# HeaderA.net
KiCad netlist of a schematic drawn in Altium Designer
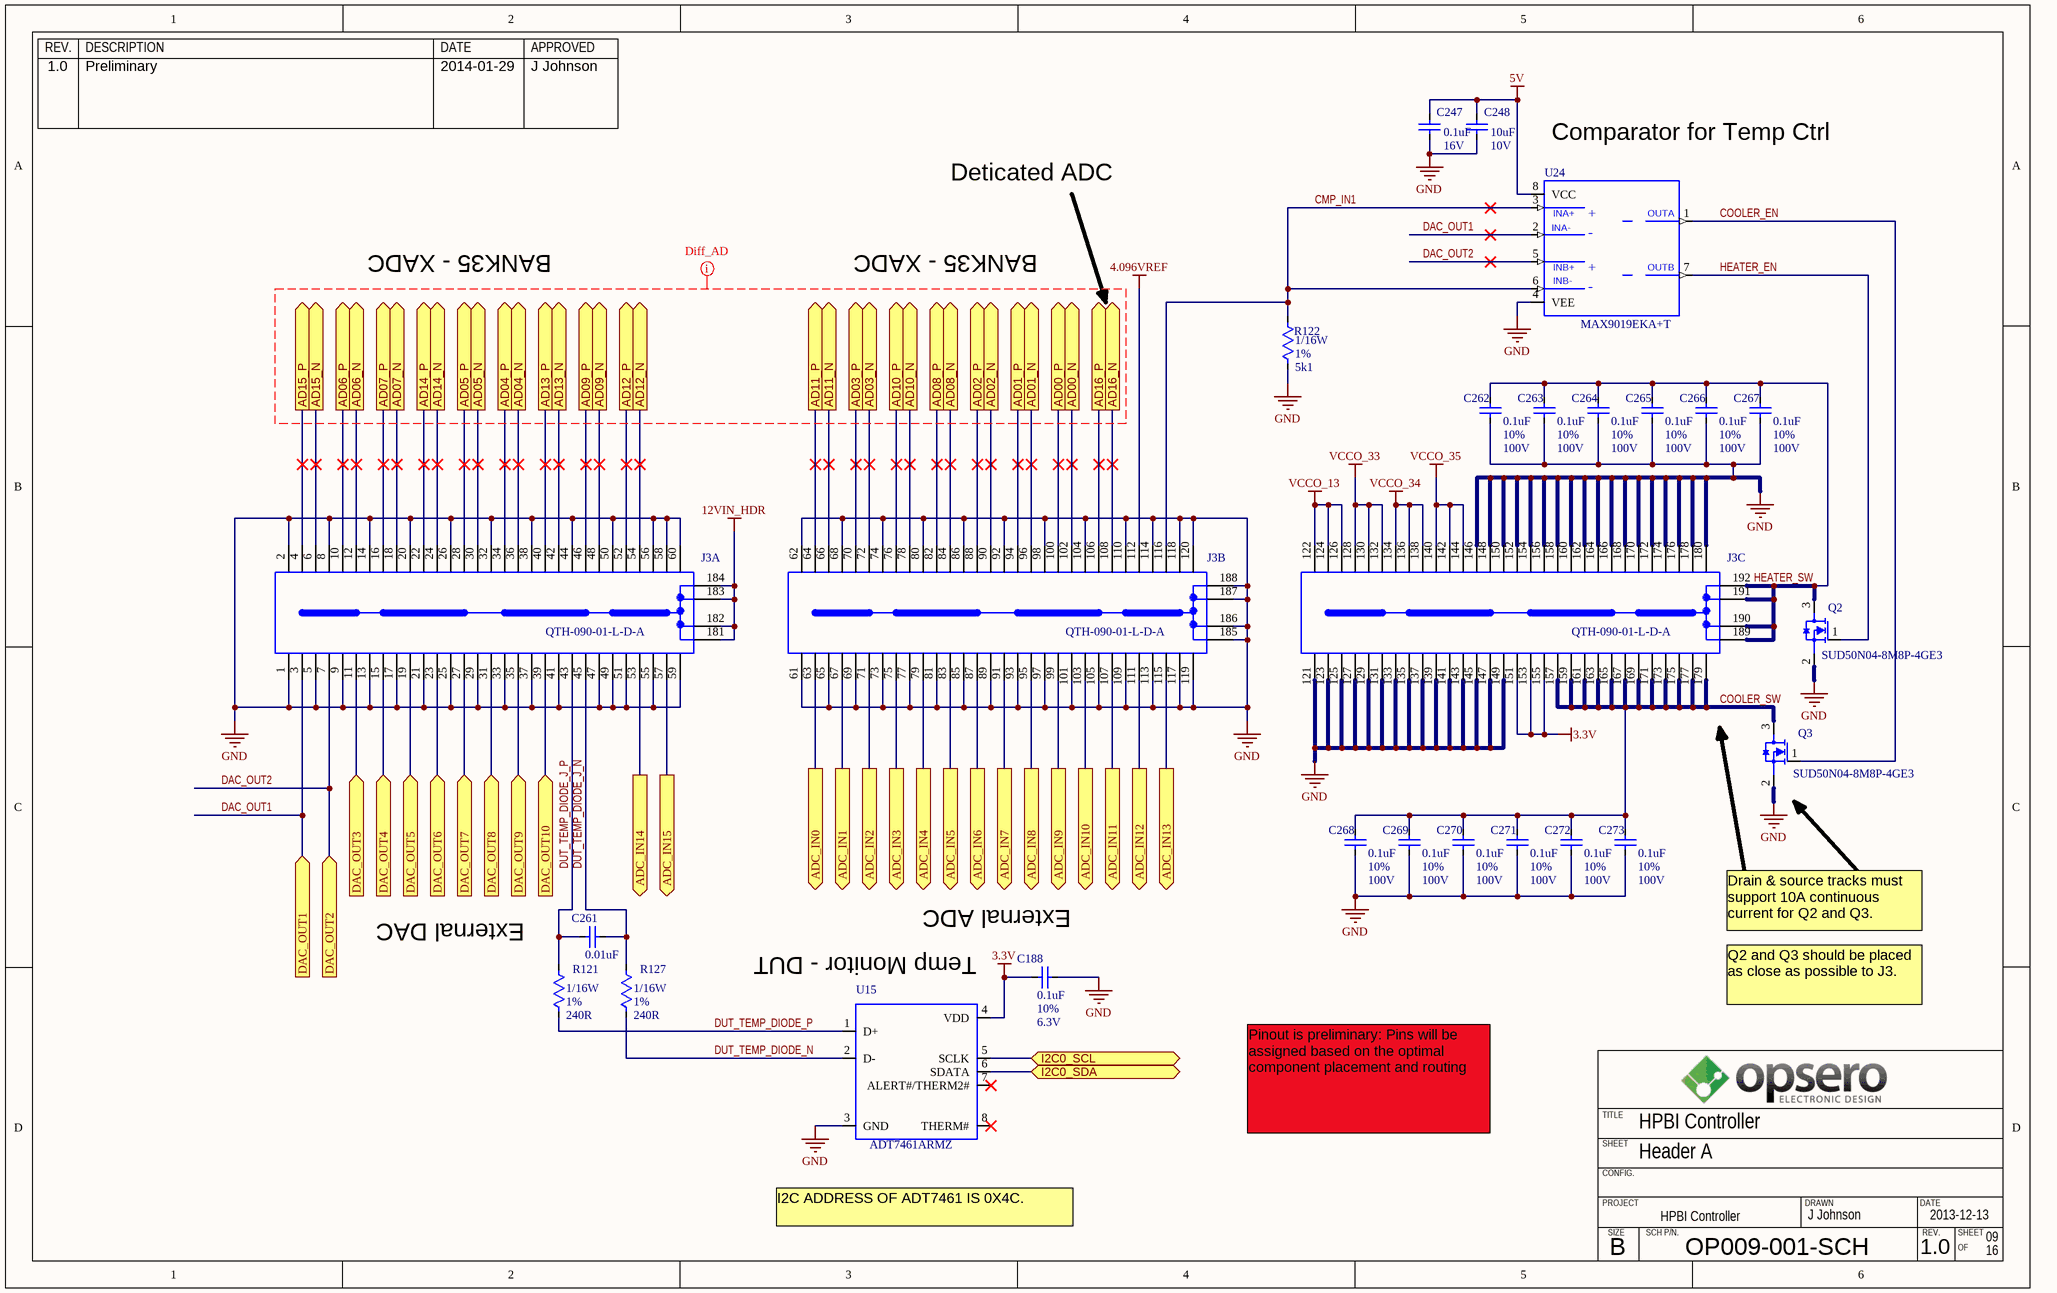
[diagram p0: HeaderA.SchDoc]

(export (version "E")
  (design (tool "Eeschema 10.0.6"))
  (components
    (comp (ref "C188")
      (value "0.1uF")
      (footprint "CAPC0603X33N")
      (description "Capacitor ceramic, X5R, 0.1uF, 6.3V, 10%, -55 to +125 C, EIA0201")
      (fields
        (field (name "TOLERANCE") "10%")
        (field (name "VOLTAGE") "6.3V")
        (field (name "Comment") "CAPACITOR_NP_TYPE1")
      )
      (libsource (lib "parts") (part "CAPACITOR_NP_TYPE1"))
    )
    (comp (ref "C247")
      (value "0.1uF")
      (footprint "CAPC1005X33N")
      (description "Capacitor ceramic, X7R, 0.1uF, 16V, 10%, -55 to +125 C, EIA0402")
      (fields
        (field (name "TOLERANCE") "10%")
        (field (name "VOLTAGE") "16V")
        (field (name "Comment") "CAPACITOR_NP_TYPE1")
      )
      (libsource (lib "parts") (part "CAPACITOR_NP_TYPE1"))
    )
    (comp (ref "C248")
      (value "10uF")
      (footprint "CAPC1608X38N")
      (description "Capacitor ceramic, X5R, 10uF, 10V, 10%, -55 to +85 C, EIA0603")
      (fields
        (field (name "TOLERANCE") "10%")
        (field (name "VOLTAGE") "10V")
        (field (name "Comment") "CAPACITOR_NP_TYPE1")
      )
      (libsource (lib "parts") (part "CAPACITOR_NP_TYPE1"))
    )
    (comp (ref "C261")
      (value "0.01uF")
      (footprint "CAPC1005X33N")
      (description "Capacitor ceramic, X7R, 0.01uF, 50V, 10%, -55 to +125 C, EIA0402")
      (fields (field (name "TOLERANCE") "10%") (field (name "VOLTAGE") "50V"))
      (libsource (lib "parts") (part "CAPACITOR_NP_TYPE1"))
    )
    (comp (ref "C262")
      (value "0.1uF")
      (footprint "CAPC1608X38N")
      (description "Capacitor ceramic, X7R, 0.1uF, 100V, 10%, -55 to +125 C, EIA0603")
      (fields
        (field (name "TOLERANCE") "10%")
        (field (name "VOLTAGE") "100V")
        (field (name "Comment") "CAPACITOR_NP_TYPE1")
      )
      (libsource (lib "parts") (part "CAPACITOR_NP_TYPE1"))
    )
    (comp (ref "C263")
      (value "0.1uF")
      (footprint "CAPC1608X38N")
      (description "Capacitor ceramic, X7R, 0.1uF, 100V, 10%, -55 to +125 C, EIA0603")
      (fields
        (field (name "TOLERANCE") "10%")
        (field (name "VOLTAGE") "100V")
        (field (name "Comment") "CAPACITOR_NP_TYPE1")
      )
      (libsource (lib "parts") (part "CAPACITOR_NP_TYPE1"))
    )
    (comp (ref "C264")
      (value "0.1uF")
      (footprint "CAPC1608X38N")
      (description "Capacitor ceramic, X7R, 0.1uF, 100V, 10%, -55 to +125 C, EIA0603")
      (fields
        (field (name "TOLERANCE") "10%")
        (field (name "VOLTAGE") "100V")
        (field (name "Comment") "CAPACITOR_NP_TYPE1")
      )
      (libsource (lib "parts") (part "CAPACITOR_NP_TYPE1"))
    )
    (comp (ref "C265")
      (value "0.1uF")
      (footprint "CAPC1608X38N")
      (description "Capacitor ceramic, X7R, 0.1uF, 100V, 10%, -55 to +125 C, EIA0603")
      (fields
        (field (name "TOLERANCE") "10%")
        (field (name "VOLTAGE") "100V")
        (field (name "Comment") "CAPACITOR_NP_TYPE1")
      )
      (libsource (lib "parts") (part "CAPACITOR_NP_TYPE1"))
    )
    (comp (ref "C266")
      (value "0.1uF")
      (footprint "CAPC1608X38N")
      (description "Capacitor ceramic, X7R, 0.1uF, 100V, 10%, -55 to +125 C, EIA0603")
      (fields
        (field (name "TOLERANCE") "10%")
        (field (name "VOLTAGE") "100V")
        (field (name "Comment") "CAPACITOR_NP_TYPE1")
      )
      (libsource (lib "parts") (part "CAPACITOR_NP_TYPE1"))
    )
    (comp (ref "C267")
      (value "0.1uF")
      (footprint "CAPC1608X38N")
      (description "Capacitor ceramic, X7R, 0.1uF, 100V, 10%, -55 to +125 C, EIA0603")
      (fields
        (field (name "TOLERANCE") "10%")
        (field (name "VOLTAGE") "100V")
        (field (name "Comment") "CAPACITOR_NP_TYPE1")
      )
      (libsource (lib "parts") (part "CAPACITOR_NP_TYPE1"))
    )
    (comp (ref "C268")
      (value "0.1uF")
      (footprint "CAPC1608X38N")
      (description "Capacitor ceramic, X7R, 0.1uF, 100V, 10%, -55 to +125 C, EIA0603")
      (fields
        (field (name "TOLERANCE") "10%")
        (field (name "VOLTAGE") "100V")
        (field (name "Comment") "CAPACITOR_NP_TYPE1")
      )
      (libsource (lib "parts") (part "CAPACITOR_NP_TYPE1"))
    )
    (comp (ref "C269")
      (value "0.1uF")
      (footprint "CAPC1608X38N")
      (description "Capacitor ceramic, X7R, 0.1uF, 100V, 10%, -55 to +125 C, EIA0603")
      (fields
        (field (name "TOLERANCE") "10%")
        (field (name "VOLTAGE") "100V")
        (field (name "Comment") "CAPACITOR_NP_TYPE1")
      )
      (libsource (lib "parts") (part "CAPACITOR_NP_TYPE1"))
    )
    (comp (ref "C270")
      (value "0.1uF")
      (footprint "CAPC1608X38N")
      (description "Capacitor ceramic, X7R, 0.1uF, 100V, 10%, -55 to +125 C, EIA0603")
      (fields
        (field (name "TOLERANCE") "10%")
        (field (name "VOLTAGE") "100V")
        (field (name "Comment") "CAPACITOR_NP_TYPE1")
      )
      (libsource (lib "parts") (part "CAPACITOR_NP_TYPE1"))
    )
    (comp (ref "C271")
      (value "0.1uF")
      (footprint "CAPC1608X38N")
      (description "Capacitor ceramic, X7R, 0.1uF, 100V, 10%, -55 to +125 C, EIA0603")
      (fields
        (field (name "TOLERANCE") "10%")
        (field (name "VOLTAGE") "100V")
        (field (name "Comment") "CAPACITOR_NP_TYPE1")
      )
      (libsource (lib "parts") (part "CAPACITOR_NP_TYPE1"))
    )
    (comp (ref "C272")
      (value "0.1uF")
      (footprint "CAPC1608X38N")
      (description "Capacitor ceramic, X7R, 0.1uF, 100V, 10%, -55 to +125 C, EIA0603")
      (fields
        (field (name "TOLERANCE") "10%")
        (field (name "VOLTAGE") "100V")
        (field (name "Comment") "CAPACITOR_NP_TYPE1")
      )
      (libsource (lib "parts") (part "CAPACITOR_NP_TYPE1"))
    )
    (comp (ref "C273")
      (value "0.1uF")
      (footprint "CAPC1608X38N")
      (description "Capacitor ceramic, X7R, 0.1uF, 100V, 10%, -55 to +125 C, EIA0603")
      (fields
        (field (name "TOLERANCE") "10%")
        (field (name "VOLTAGE") "100V")
        (field (name "Comment") "CAPACITOR_NP_TYPE1")
      )
      (libsource (lib "parts") (part "CAPACITOR_NP_TYPE1"))
    )
    (comp (ref "J3")
      (value "QTH-090-01-L-D-A")
      (footprint "QTH-090-01-L-D-A")
      (description "Connector Header HS .5mm 180 pin DL AU")
      (libsource (lib "parts") (part "QTH-090-01-L-D-A"))
    )
    (comp (ref "Q2")
      (value "SUD50N04-8M8P-4GE3")
      (footprint "TO228P1041X238-3N")
      (description "Transistor MOSFET, N-Channel, 40V, 50A, -55 to +150 C, 48W, TO-252")
      (fields (field (name "POWER") "48W") (field (name "VOLTAGE") "40V"))
      (libsource (lib "parts") (part "TRANS_MOSFET_N-CH_TYPE2"))
    )
    (comp (ref "Q3")
      (value "SUD50N04-8M8P-4GE3")
      (footprint "TO228P1041X238-3N")
      (description "Transistor MOSFET, N-Channel, 40V, 50A, -55 to +150 C, 48W, TO-252")
      (fields (field (name "POWER") "48W") (field (name "VOLTAGE") "40V"))
      (libsource (lib "parts") (part "TRANS_MOSFET_N-CH_TYPE2"))
    )
    (comp (ref "R121")
      (value "240R")
      (footprint "RESC1005X33N")
      (description "Resistor, 240R, 1/16W, 1%, -50 to +155 C, EIA0402, EIA(M)1005")
      (fields (field (name "VOLTAGE") "50V") (field (name "POWER") "1/16W") (field (name "TOLERANCE") "1%"))
      (libsource (lib "parts") (part "RESISTOR_TYPE1"))
    )
    (comp (ref "R122")
      (value "5k1")
      (footprint "RESC1005X33N")
      (description "Resistor, 5k10, 1/16W, 1%, -50 to +155 C, EIA0402, EIA(M)1005")
      (fields (field (name "VOLTAGE") "50V") (field (name "POWER") "1/16W") (field (name "TOLERANCE") "1%"))
      (libsource (lib "parts") (part "RESISTOR_TYPE1"))
    )
    (comp (ref "R127")
      (value "240R")
      (footprint "RESC1005X33N")
      (description "Resistor, 240R, 1/16W, 1%, -50 to +155 C, EIA0402, EIA(M)1005")
      (fields (field (name "VOLTAGE") "50V") (field (name "POWER") "1/16W") (field (name "TOLERANCE") "1%"))
      (libsource (lib "parts") (part "RESISTOR_TYPE1"))
    )
    (comp (ref "U15")
      (value "ADT7461ARMZ")
      (footprint "SOP65P490X110-8N")
      (description "Temperature monitor 1C, MSOP8")
      (fields (field (name "POWER") "Pow") (field (name "VOLTAGE") "Vol"))
      (libsource (lib "parts") (part "ADT7461"))
    )
    (comp (ref "U24")
      (value "MAX9019EKA+T")
      (footprint "SOT65P280X145-8AN")
      (description "Comparator, Dual, Push-pull, 1.8V to 5.5V, 50mA, -40 to +85 C, , SOT-23-8")
      (fields (field (name "POWER") "Pow") (field (name "VOLTAGE") "1.8V to 5.5V"))
      (libsource (lib "parts") (part "MAX9019"))
    )
  )
  (nets
    (net (code "1") (name "/AD00_N") (class "Default")
      (node (ref "J3") (pin "102") (pinfunction "102_102") (pintype "passive"))
    )
    (net (code "2") (name "/AD00_P") (class "Default")
      (node (ref "J3") (pin "100") (pinfunction "100_100") (pintype "passive"))
    )
    (net (code "3") (name "/AD01_N") (class "Default")
      (node (ref "J3") (pin "96") (pinfunction "96_96") (pintype "passive"))
    )
    (net (code "4") (name "/AD01_P") (class "Default")
      (node (ref "J3") (pin "94") (pinfunction "94_94") (pintype "passive"))
    )
    (net (code "5") (name "/AD02_N") (class "Default")
      (node (ref "J3") (pin "90") (pinfunction "90_90") (pintype "passive"))
    )
    (net (code "6") (name "/AD02_P") (class "Default")
      (node (ref "J3") (pin "88") (pinfunction "88_88") (pintype "passive"))
    )
    (net (code "7") (name "/AD03_N") (class "Default")
      (node (ref "J3") (pin "72") (pinfunction "72_72") (pintype "passive"))
    )
    (net (code "8") (name "/AD03_P") (class "Default")
      (node (ref "J3") (pin "70") (pinfunction "70_70") (pintype "passive"))
    )
    (net (code "9") (name "/AD04_N") (class "Default")
      (node (ref "J3") (pin "36") (pinfunction "36_36") (pintype "passive"))
    )
    (net (code "10") (name "/AD04_P") (class "Default")
      (node (ref "J3") (pin "34") (pinfunction "34_34") (pintype "passive"))
    )
    (net (code "11") (name "/AD05_N") (class "Default")
      (node (ref "J3") (pin "30") (pinfunction "30_30") (pintype "passive"))
    )
    (net (code "12") (name "/AD05_P") (class "Default")
      (node (ref "J3") (pin "28") (pinfunction "28_28") (pintype "passive"))
    )
    (net (code "13") (name "/AD06_N") (class "Default")
      (node (ref "J3") (pin "12") (pinfunction "12_12") (pintype "passive"))
    )
    (net (code "14") (name "/AD06_P") (class "Default")
      (node (ref "J3") (pin "10") (pinfunction "10_10") (pintype "passive"))
    )
    (net (code "15") (name "/AD07_N") (class "Default")
      (node (ref "J3") (pin "18") (pinfunction "18_18") (pintype "passive"))
    )
    (net (code "16") (name "/AD07_P") (class "Default")
      (node (ref "J3") (pin "16") (pinfunction "16_16") (pintype "passive"))
    )
    (net (code "17") (name "/AD08_N") (class "Default")
      (node (ref "J3") (pin "84") (pinfunction "84_84") (pintype "passive"))
    )
    (net (code "18") (name "/AD08_P") (class "Default")
      (node (ref "J3") (pin "82") (pinfunction "82_82") (pintype "passive"))
    )
    (net (code "19") (name "/AD09_N") (class "Default")
      (node (ref "J3") (pin "48") (pinfunction "48_48") (pintype "passive"))
    )
    (net (code "20") (name "/AD09_P") (class "Default")
      (node (ref "J3") (pin "46") (pinfunction "46_46") (pintype "passive"))
    )
    (net (code "21") (name "/AD10_N") (class "Default")
      (node (ref "J3") (pin "78") (pinfunction "78_78") (pintype "passive"))
    )
    (net (code "22") (name "/AD10_P") (class "Default")
      (node (ref "J3") (pin "76") (pinfunction "76_76") (pintype "passive"))
    )
    (net (code "23") (name "/AD11_N") (class "Default")
      (node (ref "J3") (pin "66") (pinfunction "66_66") (pintype "passive"))
    )
    (net (code "24") (name "/AD11_P") (class "Default")
      (node (ref "J3") (pin "64") (pinfunction "64_64") (pintype "passive"))
    )
    (net (code "25") (name "/AD12_N") (class "Default")
      (node (ref "J3") (pin "54") (pinfunction "54_54") (pintype "passive"))
    )
    (net (code "26") (name "/AD12_P") (class "Default")
      (node (ref "J3") (pin "52") (pinfunction "52_52") (pintype "passive"))
    )
    (net (code "27") (name "/AD13_N") (class "Default")
      (node (ref "J3") (pin "42") (pinfunction "42_42") (pintype "passive"))
    )
    (net (code "28") (name "/AD13_P") (class "Default")
      (node (ref "J3") (pin "40") (pinfunction "40_40") (pintype "passive"))
    )
    (net (code "29") (name "/AD14_N") (class "Default")
      (node (ref "J3") (pin "24") (pinfunction "24_24") (pintype "passive"))
    )
    (net (code "30") (name "/AD14_P") (class "Default")
      (node (ref "J3") (pin "22") (pinfunction "22_22") (pintype "passive"))
    )
    (net (code "31") (name "/AD15_N") (class "Default")
      (node (ref "J3") (pin "6") (pinfunction "6_6") (pintype "passive"))
    )
    (net (code "32") (name "/AD15_P") (class "Default")
      (node (ref "J3") (pin "4") (pinfunction "4_4") (pintype "passive"))
    )
    (net (code "33") (name "/AD16_N") (class "Default")
      (node (ref "J3") (pin "108") (pinfunction "108_108") (pintype "passive"))
    )
    (net (code "34") (name "/AD16_P") (class "Default")
      (node (ref "J3") (pin "106") (pinfunction "106_106") (pintype "passive"))
    )
    (net (code "35") (name "/ADC_IN0") (class "Default")
      (node (ref "J3") (pin "63") (pinfunction "63_63") (pintype "passive"))
    )
    (net (code "36") (name "/ADC_IN1") (class "Default")
      (node (ref "J3") (pin "67") (pinfunction "67_67") (pintype "passive"))
    )
    (net (code "37") (name "/ADC_IN2") (class "Default")
      (node (ref "J3") (pin "71") (pinfunction "71_71") (pintype "passive"))
    )
    (net (code "38") (name "/ADC_IN3") (class "Default")
      (node (ref "J3") (pin "75") (pinfunction "75_75") (pintype "passive"))
    )
    (net (code "39") (name "/ADC_IN4") (class "Default")
      (node (ref "J3") (pin "79") (pinfunction "79_79") (pintype "passive"))
    )
    (net (code "40") (name "/ADC_IN5") (class "Default")
      (node (ref "J3") (pin "83") (pinfunction "83_83") (pintype "passive"))
    )
    (net (code "41") (name "/ADC_IN6") (class "Default")
      (node (ref "J3") (pin "87") (pinfunction "87_87") (pintype "passive"))
    )
    (net (code "42") (name "/ADC_IN7") (class "Default")
      (node (ref "J3") (pin "91") (pinfunction "91_91") (pintype "passive"))
    )
    (net (code "43") (name "/ADC_IN8") (class "Default")
      (node (ref "J3") (pin "95") (pinfunction "95_95") (pintype "passive"))
    )
    (net (code "44") (name "/ADC_IN9") (class "Default")
      (node (ref "J3") (pin "99") (pinfunction "99_99") (pintype "passive"))
    )
    (net (code "45") (name "/ADC_IN10") (class "Default")
      (node (ref "J3") (pin "103") (pinfunction "103_103") (pintype "passive"))
    )
    (net (code "46") (name "/ADC_IN11") (class "Default")
      (node (ref "J3") (pin "107") (pinfunction "107_107") (pintype "passive"))
    )
    (net (code "47") (name "/ADC_IN12") (class "Default")
      (node (ref "J3") (pin "111") (pinfunction "111_111") (pintype "passive"))
    )
    (net (code "48") (name "/ADC_IN13") (class "Default")
      (node (ref "J3") (pin "115") (pinfunction "115_115") (pintype "passive"))
    )
    (net (code "49") (name "/ADC_IN14") (class "Default")
      (node (ref "J3") (pin "53") (pinfunction "53_53") (pintype "passive"))
    )
    (net (code "50") (name "/ADC_IN15") (class "Default")
      (node (ref "J3") (pin "57") (pinfunction "57_57") (pintype "passive"))
    )
    (net (code "51") (name "/CMP_IN1") (class "Default")
      (node (ref "J3") (pin "116") (pinfunction "116_116") (pintype "passive"))
      (node (ref "R122") (pin "2") (pinfunction "2_2") (pintype "passive"))
      (node (ref "U24") (pin "3") (pinfunction "INA+_3") (pintype "input"))
      (node (ref "U24") (pin "6") (pinfunction "INB-_6") (pintype "input"))
    )
    (net (code "52") (name "/COOLER_EN") (class "Default")
      (node (ref "Q3") (pin "1") (pinfunction "G_1") (pintype "passive"))
      (node (ref "U24") (pin "1") (pinfunction "OUTA_1") (pintype "output"))
    )
    (net (code "53") (name "/COOLER_SW") (class "Default")
      (node (ref "C268") (pin "1") (pinfunction "1_1") (pintype "passive"))
      (node (ref "C269") (pin "1") (pinfunction "1_1") (pintype "passive"))
      (node (ref "C270") (pin "1") (pinfunction "1_1") (pintype "passive"))
      (node (ref "C271") (pin "1") (pinfunction "1_1") (pintype "passive"))
      (node (ref "C272") (pin "1") (pinfunction "1_1") (pintype "passive"))
      (node (ref "C273") (pin "1") (pinfunction "1_1") (pintype "passive"))
      (node (ref "J3") (pin "157") (pinfunction "157_157") (pintype "passive"))
      (node (ref "J3") (pin "159") (pinfunction "159_159") (pintype "passive"))
      (node (ref "J3") (pin "161") (pinfunction "161_161") (pintype "passive"))
      (node (ref "J3") (pin "163") (pinfunction "163_163") (pintype "passive"))
      (node (ref "J3") (pin "165") (pinfunction "165_165") (pintype "passive"))
      (node (ref "J3") (pin "167") (pinfunction "167_167") (pintype "passive"))
      (node (ref "J3") (pin "169") (pinfunction "169_169") (pintype "passive"))
      (node (ref "J3") (pin "171") (pinfunction "171_171") (pintype "passive"))
      (node (ref "J3") (pin "173") (pinfunction "173_173") (pintype "passive"))
      (node (ref "J3") (pin "175") (pinfunction "175_175") (pintype "passive"))
      (node (ref "J3") (pin "177") (pinfunction "177_177") (pintype "passive"))
      (node (ref "J3") (pin "179") (pinfunction "179_179") (pintype "passive"))
      (node (ref "Q3") (pin "3") (pinfunction "D_3") (pintype "passive"))
    )
    (net (code "54") (name "/DAC_OUT1") (class "Default")
      (node (ref "J3") (pin "3") (pinfunction "3_3") (pintype "passive"))
      (node (ref "U24") (pin "2") (pinfunction "INA-_2") (pintype "input"))
    )
    (net (code "55") (name "/DAC_OUT2") (class "Default")
      (node (ref "J3") (pin "7") (pinfunction "7_7") (pintype "passive"))
      (node (ref "U24") (pin "5") (pinfunction "INB+_5") (pintype "input"))
    )
    (net (code "56") (name "/DAC_OUT3") (class "Default")
      (node (ref "J3") (pin "11") (pinfunction "11_11") (pintype "passive"))
    )
    (net (code "57") (name "/DAC_OUT4") (class "Default")
      (node (ref "J3") (pin "15") (pinfunction "15_15") (pintype "passive"))
    )
    (net (code "58") (name "/DAC_OUT5") (class "Default")
      (node (ref "J3") (pin "19") (pinfunction "19_19") (pintype "passive"))
    )
    (net (code "59") (name "/DAC_OUT6") (class "Default")
      (node (ref "J3") (pin "23") (pinfunction "23_23") (pintype "passive"))
    )
    (net (code "60") (name "/DAC_OUT7") (class "Default")
      (node (ref "J3") (pin "27") (pinfunction "27_27") (pintype "passive"))
    )
    (net (code "61") (name "/DAC_OUT8") (class "Default")
      (node (ref "J3") (pin "31") (pinfunction "31_31") (pintype "passive"))
    )
    (net (code "62") (name "/DAC_OUT9") (class "Default")
      (node (ref "J3") (pin "35") (pinfunction "35_35") (pintype "passive"))
    )
    (net (code "63") (name "/DAC_OUT10") (class "Default")
      (node (ref "J3") (pin "39") (pinfunction "39_39") (pintype "passive"))
    )
    (net (code "64") (name "/DUT_TEMP_DIODE_J_N") (class "Default")
      (node (ref "C261") (pin "2") (pinfunction "2_2") (pintype "passive"))
      (node (ref "J3") (pin "45") (pinfunction "45_45") (pintype "passive"))
      (node (ref "R127") (pin "2") (pinfunction "2_2") (pintype "passive"))
    )
    (net (code "65") (name "/DUT_TEMP_DIODE_J_P") (class "Default")
      (node (ref "C261") (pin "1") (pinfunction "1_1") (pintype "passive"))
      (node (ref "J3") (pin "43") (pinfunction "43_43") (pintype "passive"))
      (node (ref "R121") (pin "2") (pinfunction "2_2") (pintype "passive"))
    )
    (net (code "66") (name "/DUT_TEMP_DIODE_N") (class "Default")
      (node (ref "R127") (pin "1") (pinfunction "1_1") (pintype "passive"))
      (node (ref "U15") (pin "2") (pinfunction "D-_2") (pintype "passive"))
    )
    (net (code "67") (name "/DUT_TEMP_DIODE_P") (class "Default")
      (node (ref "R121") (pin "1") (pinfunction "1_1") (pintype "passive"))
      (node (ref "U15") (pin "1") (pinfunction "D+_1") (pintype "passive"))
    )
    (net (code "68") (name "/HEATER_EN") (class "Default")
      (node (ref "Q2") (pin "1") (pinfunction "G_1") (pintype "passive"))
      (node (ref "U24") (pin "7") (pinfunction "OUTB_7") (pintype "output"))
    )
    (net (code "69") (name "/HEATER_SW") (class "Default")
      (node (ref "C262") (pin "1") (pinfunction "1_1") (pintype "passive"))
      (node (ref "C263") (pin "1") (pinfunction "1_1") (pintype "passive"))
      (node (ref "C264") (pin "1") (pinfunction "1_1") (pintype "passive"))
      (node (ref "C265") (pin "1") (pinfunction "1_1") (pintype "passive"))
      (node (ref "C266") (pin "1") (pinfunction "1_1") (pintype "passive"))
      (node (ref "C267") (pin "1") (pinfunction "1_1") (pintype "passive"))
      (node (ref "J3") (pin "189") (pinfunction "189_189") (pintype "passive"))
      (node (ref "J3") (pin "190") (pinfunction "190_190") (pintype "passive"))
      (node (ref "J3") (pin "191") (pinfunction "191_191") (pintype "passive"))
      (node (ref "J3") (pin "192") (pinfunction "192_192") (pintype "passive"))
      (node (ref "Q2") (pin "3") (pinfunction "D_3") (pintype "passive"))
    )
    (net (code "70") (name "/I2C0_SCL") (class "Default")
      (node (ref "U15") (pin "5") (pinfunction "SCLK_5") (pintype "passive"))
    )
    (net (code "71") (name "/I2C0_SDA") (class "Default")
      (node (ref "U15") (pin "6") (pinfunction "SDATA_6") (pintype "passive"))
    )
    (net (code "72") (name "3.3V") (class "Default")
      (node (ref "C188") (pin "1") (pinfunction "1_1") (pintype "passive"))
      (node (ref "J3") (pin "151") (pinfunction "151_151") (pintype "passive"))
      (node (ref "J3") (pin "153") (pinfunction "153_153") (pintype "passive"))
      (node (ref "J3") (pin "155") (pinfunction "155_155") (pintype "passive"))
      (node (ref "U15") (pin "4") (pinfunction "VDD_4") (pintype "passive"))
    )
    (net (code "73") (name "4.096VREF") (class "Default")
      (node (ref "J3") (pin "112") (pinfunction "112_112") (pintype "passive"))
    )
    (net (code "74") (name "5V") (class "Default")
      (node (ref "C247") (pin "1") (pinfunction "1_1") (pintype "passive"))
      (node (ref "C248") (pin "1") (pinfunction "1_1") (pintype "passive"))
      (node (ref "U24") (pin "8") (pinfunction "VCC_8") (pintype "power_in"))
    )
    (net (code "75") (name "12VIN_HDR") (class "Default")
      (node (ref "J3") (pin "181") (pinfunction "181_181") (pintype "passive"))
      (node (ref "J3") (pin "182") (pinfunction "182_182") (pintype "passive"))
      (node (ref "J3") (pin "183") (pinfunction "183_183") (pintype "passive"))
      (node (ref "J3") (pin "184") (pinfunction "184_184") (pintype "passive"))
    )
    (net (code "76") (name "GND") (class "Default")
      (node (ref "C188") (pin "2") (pinfunction "2_2") (pintype "passive"))
      (node (ref "C247") (pin "2") (pinfunction "2_2") (pintype "passive"))
      (node (ref "C248") (pin "2") (pinfunction "2_2") (pintype "passive"))
      (node (ref "C262") (pin "2") (pinfunction "2_2") (pintype "passive"))
      (node (ref "C263") (pin "2") (pinfunction "2_2") (pintype "passive"))
      (node (ref "C264") (pin "2") (pinfunction "2_2") (pintype "passive"))
      (node (ref "C265") (pin "2") (pinfunction "2_2") (pintype "passive"))
      (node (ref "C266") (pin "2") (pinfunction "2_2") (pintype "passive"))
      (node (ref "C267") (pin "2") (pinfunction "2_2") (pintype "passive"))
      (node (ref "C268") (pin "2") (pinfunction "2_2") (pintype "passive"))
      (node (ref "C269") (pin "2") (pinfunction "2_2") (pintype "passive"))
      (node (ref "C270") (pin "2") (pinfunction "2_2") (pintype "passive"))
      (node (ref "C271") (pin "2") (pinfunction "2_2") (pintype "passive"))
      (node (ref "C272") (pin "2") (pinfunction "2_2") (pintype "passive"))
      (node (ref "C273") (pin "2") (pinfunction "2_2") (pintype "passive"))
      (node (ref "J3") (pin "1") (pinfunction "1_1") (pintype "passive"))
      (node (ref "J3") (pin "101") (pinfunction "101_101") (pintype "passive"))
      (node (ref "J3") (pin "104") (pinfunction "104_104") (pintype "passive"))
      (node (ref "J3") (pin "105") (pinfunction "105_105") (pintype "passive"))
      (node (ref "J3") (pin "109") (pinfunction "109_109") (pintype "passive"))
      (node (ref "J3") (pin "110") (pinfunction "110_110") (pintype "passive"))
      (node (ref "J3") (pin "113") (pinfunction "113_113") (pintype "passive"))
      (node (ref "J3") (pin "114") (pinfunction "114_114") (pintype "passive"))
      (node (ref "J3") (pin "117") (pinfunction "117_117") (pintype "passive"))
      (node (ref "J3") (pin "118") (pinfunction "118_118") (pintype "passive"))
      (node (ref "J3") (pin "119") (pinfunction "119_119") (pintype "passive"))
      (node (ref "J3") (pin "120") (pinfunction "120_120") (pintype "passive"))
      (node (ref "J3") (pin "121") (pinfunction "121_121") (pintype "passive"))
      (node (ref "J3") (pin "123") (pinfunction "123_123") (pintype "passive"))
      (node (ref "J3") (pin "125") (pinfunction "125_125") (pintype "passive"))
      (node (ref "J3") (pin "127") (pinfunction "127_127") (pintype "passive"))
      (node (ref "J3") (pin "129") (pinfunction "129_129") (pintype "passive"))
      (node (ref "J3") (pin "13") (pinfunction "13_13") (pintype "passive"))
      (node (ref "J3") (pin "131") (pinfunction "131_131") (pintype "passive"))
      (node (ref "J3") (pin "133") (pinfunction "133_133") (pintype "passive"))
      (node (ref "J3") (pin "135") (pinfunction "135_135") (pintype "passive"))
      (node (ref "J3") (pin "137") (pinfunction "137_137") (pintype "passive"))
      (node (ref "J3") (pin "139") (pinfunction "139_139") (pintype "passive"))
      (node (ref "J3") (pin "14") (pinfunction "14_14") (pintype "passive"))
      (node (ref "J3") (pin "141") (pinfunction "141_141") (pintype "passive"))
      (node (ref "J3") (pin "143") (pinfunction "143_143") (pintype "passive"))
      (node (ref "J3") (pin "145") (pinfunction "145_145") (pintype "passive"))
      (node (ref "J3") (pin "146") (pinfunction "146_146") (pintype "passive"))
      (node (ref "J3") (pin "147") (pinfunction "147_147") (pintype "passive"))
      (node (ref "J3") (pin "148") (pinfunction "148_148") (pintype "passive"))
      (node (ref "J3") (pin "149") (pinfunction "149_149") (pintype "passive"))
      (node (ref "J3") (pin "150") (pinfunction "150_150") (pintype "passive"))
      (node (ref "J3") (pin "152") (pinfunction "152_152") (pintype "passive"))
      (node (ref "J3") (pin "154") (pinfunction "154_154") (pintype "passive"))
      (node (ref "J3") (pin "156") (pinfunction "156_156") (pintype "passive"))
      (node (ref "J3") (pin "158") (pinfunction "158_158") (pintype "passive"))
      (node (ref "J3") (pin "160") (pinfunction "160_160") (pintype "passive"))
      (node (ref "J3") (pin "162") (pinfunction "162_162") (pintype "passive"))
      (node (ref "J3") (pin "164") (pinfunction "164_164") (pintype "passive"))
      (node (ref "J3") (pin "166") (pinfunction "166_166") (pintype "passive"))
      (node (ref "J3") (pin "168") (pinfunction "168_168") (pintype "passive"))
      (node (ref "J3") (pin "17") (pinfunction "17_17") (pintype "passive"))
      (node (ref "J3") (pin "170") (pinfunction "170_170") (pintype "passive"))
      (node (ref "J3") (pin "172") (pinfunction "172_172") (pintype "passive"))
      (node (ref "J3") (pin "174") (pinfunction "174_174") (pintype "passive"))
      (node (ref "J3") (pin "176") (pinfunction "176_176") (pintype "passive"))
      (node (ref "J3") (pin "178") (pinfunction "178_178") (pintype "passive"))
      (node (ref "J3") (pin "180") (pinfunction "180_180") (pintype "passive"))
      (node (ref "J3") (pin "185") (pinfunction "185_185") (pintype "passive"))
      (node (ref "J3") (pin "186") (pinfunction "186_186") (pintype "passive"))
      (node (ref "J3") (pin "187") (pinfunction "187_187") (pintype "passive"))
      (node (ref "J3") (pin "188") (pinfunction "188_188") (pintype "passive"))
      (node (ref "J3") (pin "2") (pinfunction "2_2") (pintype "passive"))
      (node (ref "J3") (pin "20") (pinfunction "20_20") (pintype "passive"))
      (node (ref "J3") (pin "21") (pinfunction "21_21") (pintype "passive"))
      (node (ref "J3") (pin "25") (pinfunction "25_25") (pintype "passive"))
      (node (ref "J3") (pin "26") (pinfunction "26_26") (pintype "passive"))
      (node (ref "J3") (pin "29") (pinfunction "29_29") (pintype "passive"))
      (node (ref "J3") (pin "32") (pinfunction "32_32") (pintype "passive"))
      (node (ref "J3") (pin "33") (pinfunction "33_33") (pintype "passive"))
      (node (ref "J3") (pin "37") (pinfunction "37_37") (pintype "passive"))
      (node (ref "J3") (pin "38") (pinfunction "38_38") (pintype "passive"))
      (node (ref "J3") (pin "41") (pinfunction "41_41") (pintype "passive"))
      (node (ref "J3") (pin "44") (pinfunction "44_44") (pintype "passive"))
      (node (ref "J3") (pin "47") (pinfunction "47_47") (pintype "passive"))
      (node (ref "J3") (pin "49") (pinfunction "49_49") (pintype "passive"))
      (node (ref "J3") (pin "5") (pinfunction "5_5") (pintype "passive"))
      (node (ref "J3") (pin "50") (pinfunction "50_50") (pintype "passive"))
      (node (ref "J3") (pin "51") (pinfunction "51_51") (pintype "passive"))
      (node (ref "J3") (pin "55") (pinfunction "55_55") (pintype "passive"))
      (node (ref "J3") (pin "56") (pinfunction "56_56") (pintype "passive"))
      (node (ref "J3") (pin "58") (pinfunction "58_58") (pintype "passive"))
      (node (ref "J3") (pin "59") (pinfunction "59_59") (pintype "passive"))
      (node (ref "J3") (pin "60") (pinfunction "60_60") (pintype "passive"))
      (node (ref "J3") (pin "61") (pinfunction "61_61") (pintype "passive"))
      (node (ref "J3") (pin "62") (pinfunction "62_62") (pintype "passive"))
      (node (ref "J3") (pin "65") (pinfunction "65_65") (pintype "passive"))
      (node (ref "J3") (pin "68") (pinfunction "68_68") (pintype "passive"))
      (node (ref "J3") (pin "69") (pinfunction "69_69") (pintype "passive"))
      (node (ref "J3") (pin "73") (pinfunction "73_73") (pintype "passive"))
      (node (ref "J3") (pin "74") (pinfunction "74_74") (pintype "passive"))
      (node (ref "J3") (pin "77") (pinfunction "77_77") (pintype "passive"))
      (node (ref "J3") (pin "8") (pinfunction "8_8") (pintype "passive"))
      (node (ref "J3") (pin "80") (pinfunction "80_80") (pintype "passive"))
      (node (ref "J3") (pin "81") (pinfunction "81_81") (pintype "passive"))
      (node (ref "J3") (pin "85") (pinfunction "85_85") (pintype "passive"))
      (node (ref "J3") (pin "86") (pinfunction "86_86") (pintype "passive"))
      (node (ref "J3") (pin "89") (pinfunction "89_89") (pintype "passive"))
      (node (ref "J3") (pin "9") (pinfunction "9_9") (pintype "passive"))
      (node (ref "J3") (pin "92") (pinfunction "92_92") (pintype "passive"))
      (node (ref "J3") (pin "93") (pinfunction "93_93") (pintype "passive"))
      (node (ref "J3") (pin "97") (pinfunction "97_97") (pintype "passive"))
      (node (ref "J3") (pin "98") (pinfunction "98_98") (pintype "passive"))
      (node (ref "Q2") (pin "2") (pinfunction "S_2") (pintype "passive"))
      (node (ref "Q3") (pin "2") (pinfunction "S_2") (pintype "passive"))
      (node (ref "R122") (pin "1") (pinfunction "1_1") (pintype "passive"))
      (node (ref "U15") (pin "3") (pinfunction "GND_3") (pintype "passive"))
      (node (ref "U24") (pin "4") (pinfunction "VEE_4") (pintype "power_in"))
    )
    (net (code "77") (name "VCCO_13") (class "Default")
      (node (ref "J3") (pin "122") (pinfunction "122_122") (pintype "passive"))
      (node (ref "J3") (pin "124") (pinfunction "124_124") (pintype "passive"))
      (node (ref "J3") (pin "126") (pinfunction "126_126") (pintype "passive"))
    )
    (net (code "78") (name "VCCO_33") (class "Default")
      (node (ref "J3") (pin "128") (pinfunction "128_128") (pintype "passive"))
      (node (ref "J3") (pin "130") (pinfunction "130_130") (pintype "passive"))
      (node (ref "J3") (pin "132") (pinfunction "132_132") (pintype "passive"))
    )
    (net (code "79") (name "VCCO_34") (class "Default")
      (node (ref "J3") (pin "134") (pinfunction "134_134") (pintype "passive"))
      (node (ref "J3") (pin "136") (pinfunction "136_136") (pintype "passive"))
      (node (ref "J3") (pin "138") (pinfunction "138_138") (pintype "passive"))
    )
    (net (code "80") (name "VCCO_35") (class "Default")
      (node (ref "J3") (pin "140") (pinfunction "140_140") (pintype "passive"))
      (node (ref "J3") (pin "142") (pinfunction "142_142") (pintype "passive"))
      (node (ref "J3") (pin "144") (pinfunction "144_144") (pintype "passive"))
    )
    (net (code "81") (name "unconnected-(U15-ALERT#{slash}THERM2#-Pad7)") (class "Default")
      (node (ref "U15") (pin "7") (pinfunction "ALERT#/THERM2#_7") (pintype "passive+no_connect"))
    )
    (net (code "82") (name "unconnected-(U15-THERM#-Pad8)") (class "Default")
      (node (ref "U15") (pin "8") (pinfunction "THERM#_8") (pintype "passive+no_connect"))
    )
  )
)
